# working.net
KiCad netlist of a schematic drawn in EAGLE
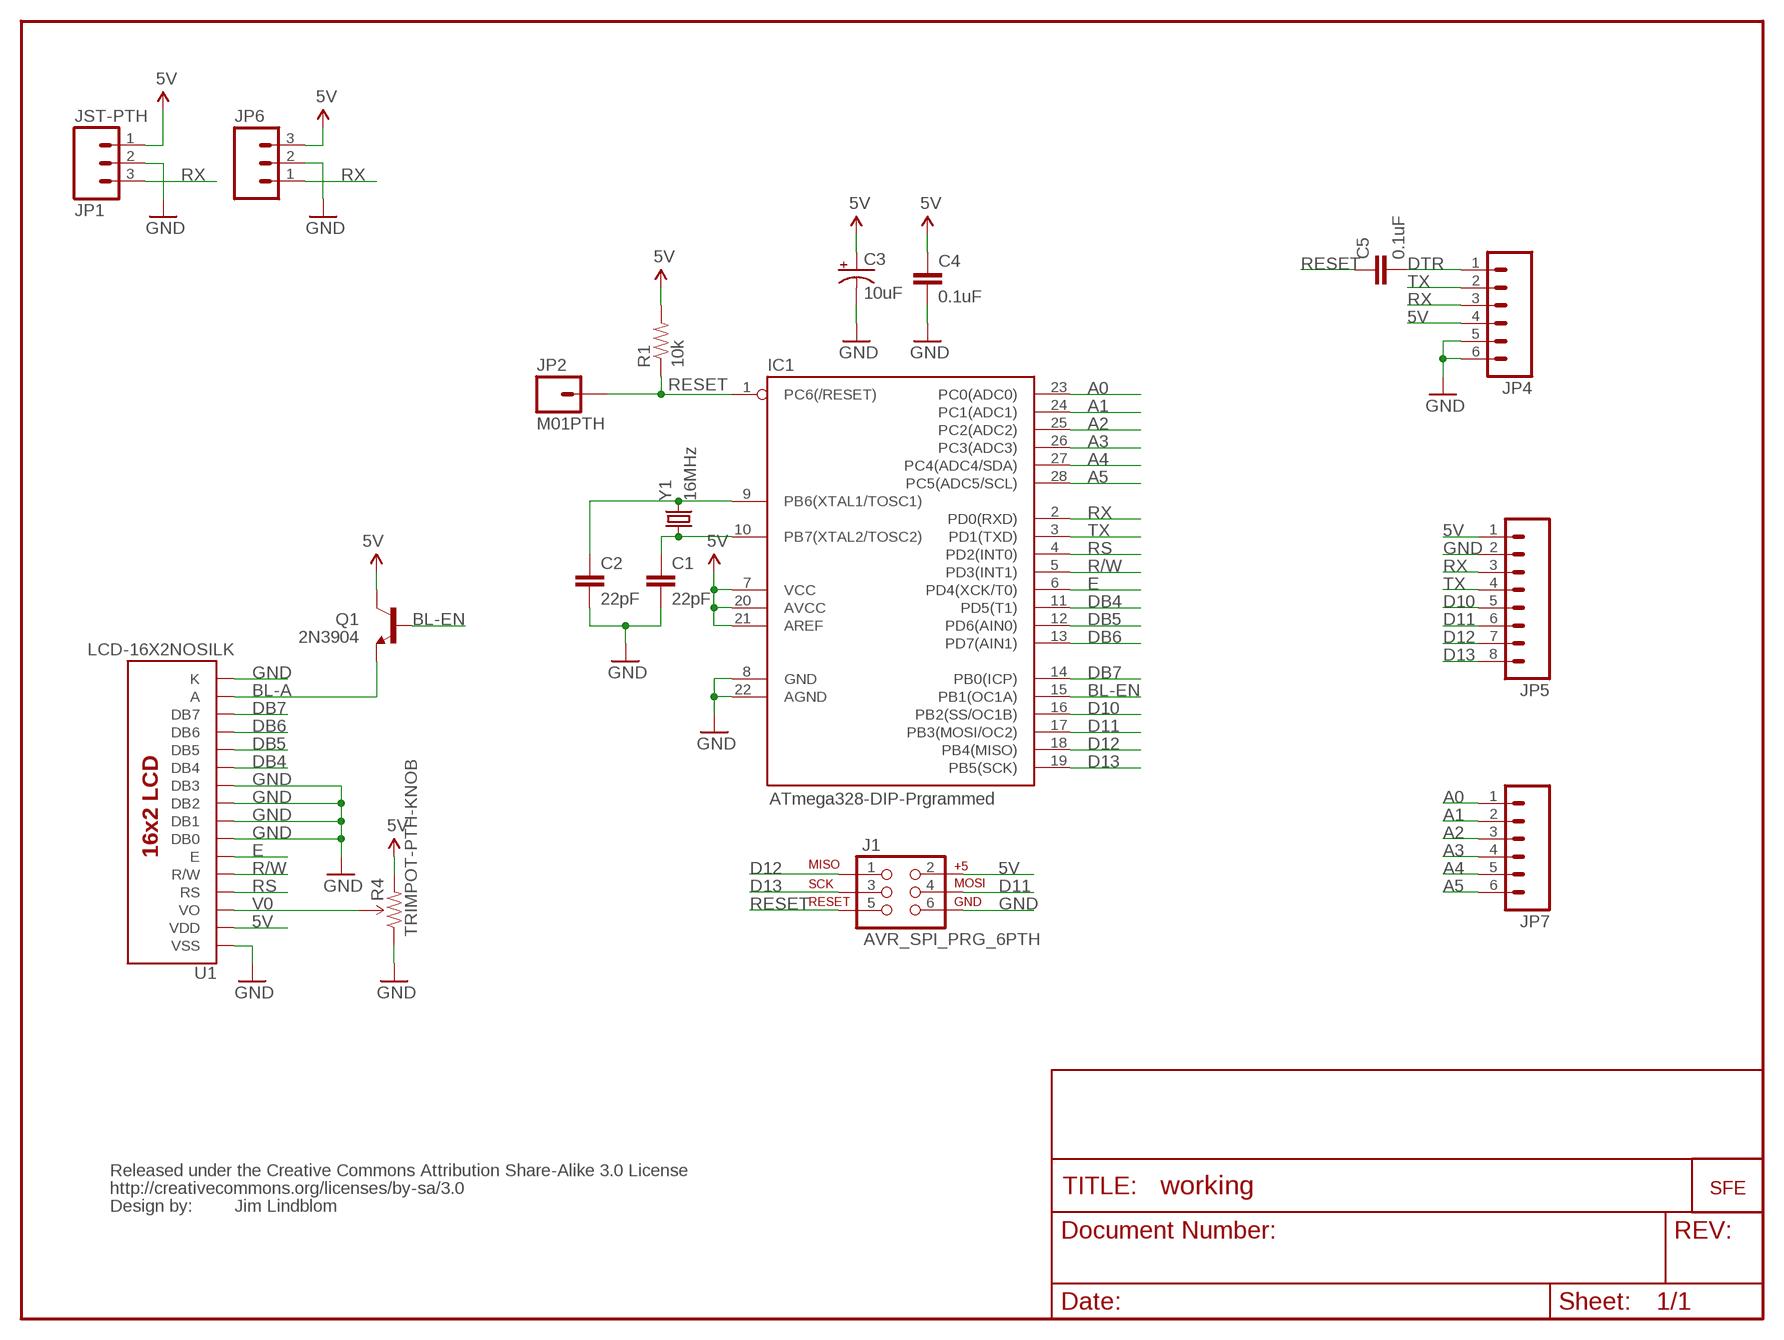
[diagram p0: schematic, sheet 1]

(export (version "E")
  (design (tool "Eeschema 10.0.6"))
  (components
    (comp (ref "C1")
      (value "22pF")
      (footprint "eagle-import:CAP-PTH-SMALL2")
      (libsource (lib "eagle-import") (part "CAPPTH2"))
    )
    (comp (ref "C2")
      (value "22pF")
      (footprint "eagle-import:CAP-PTH-SMALL2")
      (libsource (lib "eagle-import") (part "CAPPTH2"))
    )
    (comp (ref "C3")
      (value "10uF")
      (footprint "eagle-import:CPOL-RADIAL-10UF-25V")
      (libsource (lib "eagle-import") (part "CAP_POLPTH2"))
    )
    (comp (ref "C4")
      (value "0.1uF")
      (footprint "eagle-import:CAP-PTH-SMALL2")
      (libsource (lib "eagle-import") (part "CAPPTH2"))
    )
    (comp (ref "C5")
      (value "0.1uF")
      (footprint "eagle-import:CAP-PTH-SMALL2")
      (libsource (lib "eagle-import") (part "CAPPTH2"))
    )
    (comp (ref "IC1")
      (value "ATmega328-DIP-Prgrammed")
      (footprint "eagle-import:DIL28-3")
      (libsource (lib "eagle-import") (part "AVR-MEGA8-PPTH"))
    )
    (comp (ref "J1")
      (value "AVR_SPI_PRG_6PTH")
      (footprint "eagle-import:2X3")
      (libsource (lib "eagle-import") (part "AVR_SPI_PRG_6PTH"))
    )
    (comp (ref "JP1")
      (value "JST-PTH")
      (footprint "eagle-import:JST-3-PTH")
      (libsource (lib "eagle-import") (part "M03JST-PTH"))
    )
    (comp (ref "JP2")
      (value "M01PTH")
      (footprint "eagle-import:1X01")
      (libsource (lib "eagle-import") (part "M01PTH"))
    )
    (comp (ref "JP3")
      (value "LOGO-SFENEW")
      (footprint "eagle-import:SFE-NEW-WEBLOGO")
      (libsource (lib "eagle-import") (part "LOGO-SFENEW"))
    )
    (comp (ref "JP4")
      (value "M06SIP")
      (footprint "eagle-import:1X06")
      (libsource (lib "eagle-import") (part "M06SIP"))
    )
    (comp (ref "JP5")
      (value "M08")
      (footprint "eagle-import:1X08")
      (libsource (lib "eagle-import") (part "M08"))
    )
    (comp (ref "JP6")
      (value "M03PTH")
      (footprint "eagle-import:1X03")
      (libsource (lib "eagle-import") (part "M03PTH"))
    )
    (comp (ref "JP7")
      (value "M06SIP")
      (footprint "eagle-import:1X06")
      (libsource (lib "eagle-import") (part "M06SIP"))
    )
    (comp (ref "Q1")
      (value "2N3904")
      (footprint "eagle-import:TO-92")
      (libsource (lib "eagle-import") (part "TRANSISTOR_NPNTO92"))
    )
    (comp (ref "R1")
      (value "10k")
      (footprint "eagle-import:AXIAL-0.3")
      (libsource (lib "eagle-import") (part "RESISTORAXIAL-0.3"))
    )
    (comp (ref "R4")
      (value "TRIMPOT-PTH-KNOB")
      (footprint "eagle-import:3386U")
      (libsource (lib "eagle-import") (part "TRIMPOT-PTH-KNOB"))
    )
    (comp (ref "U$4")
      (value "CREATIVE_COMMONS")
      (footprint "eagle-import:CREATIVE_COMMONS")
      (libsource (lib "eagle-import") (part "CREATIVE_COMMONS"))
    )
    (comp (ref "U1")
      (value "LCD-16X2NOSILK")
      (footprint "eagle-import:LCD-16X2_NOSILK")
      (libsource (lib "eagle-import") (part "LCD-16X2NOSILK"))
    )
    (comp (ref "Y1")
      (value "16MHz")
      (footprint "eagle-import:HC49US")
      (libsource (lib "eagle-import") (part "CRYSTALHC49US"))
    )
  )
  (nets
    (net (code "1") (name "/A0") (class "Default")
      (node (ref "IC1") (pin "23") (pinfunction "PC0(ADC0)_23") (pintype "bidirectional"))
      (node (ref "JP7") (pin "1") (pinfunction "1_1") (pintype "passive"))
    )
    (net (code "2") (name "/A1") (class "Default")
      (node (ref "IC1") (pin "24") (pinfunction "PC1(ADC1)_24") (pintype "bidirectional"))
      (node (ref "JP7") (pin "2") (pinfunction "2_2") (pintype "passive"))
    )
    (net (code "3") (name "/A2") (class "Default")
      (node (ref "IC1") (pin "25") (pinfunction "PC2(ADC2)_25") (pintype "bidirectional"))
      (node (ref "JP7") (pin "3") (pinfunction "3_3") (pintype "passive"))
    )
    (net (code "4") (name "/A3") (class "Default")
      (node (ref "IC1") (pin "26") (pinfunction "PC3(ADC3)_26") (pintype "bidirectional"))
      (node (ref "JP7") (pin "4") (pinfunction "4_4") (pintype "passive"))
    )
    (net (code "5") (name "/A4") (class "Default")
      (node (ref "IC1") (pin "27") (pinfunction "PC4(ADC4/SDA)_27") (pintype "bidirectional"))
      (node (ref "JP7") (pin "5") (pinfunction "5_5") (pintype "passive"))
    )
    (net (code "6") (name "/A5") (class "Default")
      (node (ref "IC1") (pin "28") (pinfunction "PC5(ADC5/SCL)_28") (pintype "bidirectional"))
      (node (ref "JP7") (pin "6") (pinfunction "6_6") (pintype "passive"))
    )
    (net (code "7") (name "/BL-A") (class "Default")
      (node (ref "Q1") (pin "1") (pinfunction "E_1") (pintype "passive"))
      (node (ref "U1") (pin "15") (pinfunction "A_15") (pintype "power_in"))
    )
    (net (code "8") (name "/BL-EN") (class "Default")
      (node (ref "IC1") (pin "15") (pinfunction "PB1(OC1A)_15") (pintype "bidirectional"))
      (node (ref "Q1") (pin "2") (pinfunction "B_2") (pintype "passive"))
    )
    (net (code "9") (name "/D10") (class "Default")
      (node (ref "IC1") (pin "16") (pinfunction "PB2(SS/OC1B)_16") (pintype "bidirectional"))
      (node (ref "JP5") (pin "5") (pinfunction "5_5") (pintype "passive"))
    )
    (net (code "10") (name "/D11") (class "Default")
      (node (ref "IC1") (pin "17") (pinfunction "PB3(MOSI/OC2)_17") (pintype "bidirectional"))
      (node (ref "J1") (pin "4") (pinfunction "4_4") (pintype "passive"))
      (node (ref "JP5") (pin "6") (pinfunction "6_6") (pintype "passive"))
    )
    (net (code "11") (name "/D12") (class "Default")
      (node (ref "IC1") (pin "18") (pinfunction "PB4(MISO)_18") (pintype "bidirectional"))
      (node (ref "J1") (pin "1") (pinfunction "1_1") (pintype "passive"))
      (node (ref "JP5") (pin "7") (pinfunction "7_7") (pintype "passive"))
    )
    (net (code "12") (name "/D13") (class "Default")
      (node (ref "IC1") (pin "19") (pinfunction "PB5(SCK)_19") (pintype "bidirectional"))
      (node (ref "J1") (pin "3") (pinfunction "3_3") (pintype "passive"))
      (node (ref "JP5") (pin "8") (pinfunction "8_8") (pintype "passive"))
    )
    (net (code "13") (name "/DB4") (class "Default")
      (node (ref "IC1") (pin "11") (pinfunction "PD5(T1)_11") (pintype "bidirectional"))
      (node (ref "U1") (pin "11") (pinfunction "DB4_11") (pintype "bidirectional"))
    )
    (net (code "14") (name "/DB5") (class "Default")
      (node (ref "IC1") (pin "12") (pinfunction "PD6(AIN0)_12") (pintype "bidirectional"))
      (node (ref "U1") (pin "12") (pinfunction "DB5_12") (pintype "bidirectional"))
    )
    (net (code "15") (name "/DB6") (class "Default")
      (node (ref "IC1") (pin "13") (pinfunction "PD7(AIN1)_13") (pintype "bidirectional"))
      (node (ref "U1") (pin "13") (pinfunction "DB6_13") (pintype "bidirectional"))
    )
    (net (code "16") (name "/DB7") (class "Default")
      (node (ref "IC1") (pin "14") (pinfunction "PB0(ICP)_14") (pintype "bidirectional"))
      (node (ref "U1") (pin "14") (pinfunction "DB7_14") (pintype "bidirectional"))
    )
    (net (code "17") (name "/DTR") (class "Default")
      (node (ref "C5") (pin "2") (pinfunction "2_2") (pintype "passive"))
      (node (ref "JP4") (pin "1") (pinfunction "1_1") (pintype "passive"))
    )
    (net (code "18") (name "/E") (class "Default")
      (node (ref "IC1") (pin "6") (pinfunction "PD4(XCK/T0)_6") (pintype "bidirectional"))
      (node (ref "U1") (pin "6") (pinfunction "E_6") (pintype "input"))
    )
    (net (code "19") (name "/RESET") (class "Default")
      (node (ref "C5") (pin "1") (pinfunction "1_1") (pintype "passive"))
      (node (ref "IC1") (pin "1") (pinfunction "PC6(/RESET)_1") (pintype "bidirectional"))
      (node (ref "J1") (pin "5") (pinfunction "5_5") (pintype "passive"))
      (node (ref "JP2") (pin "1") (pinfunction "1_1") (pintype "passive"))
      (node (ref "R1") (pin "P$1") (pinfunction "1_P$1") (pintype "passive"))
    )
    (net (code "20") (name "/RS") (class "Default")
      (node (ref "IC1") (pin "4") (pinfunction "PD2(INT0)_4") (pintype "bidirectional"))
      (node (ref "U1") (pin "4") (pinfunction "RS_4") (pintype "input"))
    )
    (net (code "21") (name "/RX") (class "Default")
      (node (ref "IC1") (pin "2") (pinfunction "PD0(RXD)_2") (pintype "bidirectional"))
      (node (ref "JP1") (pin "3") (pinfunction "3_3") (pintype "passive"))
      (node (ref "JP4") (pin "3") (pinfunction "3_3") (pintype "passive"))
      (node (ref "JP5") (pin "3") (pinfunction "3_3") (pintype "passive"))
      (node (ref "JP6") (pin "1") (pinfunction "1_1") (pintype "passive"))
    )
    (net (code "22") (name "/R{slash}W") (class "Default")
      (node (ref "IC1") (pin "5") (pinfunction "PD3(INT1)_5") (pintype "bidirectional"))
      (node (ref "U1") (pin "5") (pinfunction "R/W_5") (pintype "input"))
    )
    (net (code "23") (name "/TX") (class "Default")
      (node (ref "IC1") (pin "3") (pinfunction "PD1(TXD)_3") (pintype "bidirectional"))
      (node (ref "JP4") (pin "2") (pinfunction "2_2") (pintype "passive"))
      (node (ref "JP5") (pin "4") (pinfunction "4_4") (pintype "passive"))
    )
    (net (code "24") (name "/V0") (class "Default")
      (node (ref "R4") (pin "2") (pinfunction "WIPER_2") (pintype "passive"))
      (node (ref "U1") (pin "3") (pinfunction "VO_3") (pintype "bidirectional"))
    )
    (net (code "25") (name "5V") (class "Default")
      (node (ref "C3") (pin "1") (pinfunction "+_1") (pintype "passive"))
      (node (ref "C4") (pin "1") (pinfunction "1_1") (pintype "passive"))
      (node (ref "IC1") (pin "20") (pinfunction "AVCC_20") (pintype "bidirectional"))
      (node (ref "IC1") (pin "21") (pinfunction "AREF_21") (pintype "bidirectional"))
      (node (ref "IC1") (pin "7") (pinfunction "VCC_7") (pintype "bidirectional"))
      (node (ref "J1") (pin "2") (pinfunction "2_2") (pintype "passive"))
      (node (ref "JP1") (pin "1") (pinfunction "1_1") (pintype "passive"))
      (node (ref "JP4") (pin "4") (pinfunction "4_4") (pintype "passive"))
      (node (ref "JP5") (pin "1") (pinfunction "1_1") (pintype "passive"))
      (node (ref "JP6") (pin "3") (pinfunction "3_3") (pintype "passive"))
      (node (ref "Q1") (pin "3") (pinfunction "C_3") (pintype "passive"))
      (node (ref "R1") (pin "P$2") (pinfunction "2_P$2") (pintype "passive"))
      (node (ref "R4") (pin "3") (pinfunction "CW_3") (pintype "passive"))
      (node (ref "U1") (pin "2") (pinfunction "VDD_2") (pintype "power_in"))
    )
    (net (code "26") (name "GND") (class "Default")
      (node (ref "C1") (pin "2") (pinfunction "2_2") (pintype "passive"))
      (node (ref "C2") (pin "2") (pinfunction "2_2") (pintype "passive"))
      (node (ref "C3") (pin "2") (pinfunction "-_2") (pintype "passive"))
      (node (ref "C4") (pin "2") (pinfunction "2_2") (pintype "passive"))
      (node (ref "IC1") (pin "22") (pinfunction "AGND_22") (pintype "bidirectional"))
      (node (ref "IC1") (pin "8") (pinfunction "GND_8") (pintype "bidirectional"))
      (node (ref "J1") (pin "6") (pinfunction "6_6") (pintype "passive"))
      (node (ref "JP1") (pin "2") (pinfunction "2_2") (pintype "passive"))
      (node (ref "JP4") (pin "5") (pinfunction "5_5") (pintype "passive"))
      (node (ref "JP4") (pin "6") (pinfunction "6_6") (pintype "passive"))
      (node (ref "JP5") (pin "2") (pinfunction "2_2") (pintype "passive"))
      (node (ref "JP6") (pin "2") (pinfunction "2_2") (pintype "passive"))
      (node (ref "R4") (pin "1") (pinfunction "CCW_1") (pintype "passive"))
      (node (ref "U1") (pin "1") (pinfunction "VSS_1") (pintype "power_in"))
      (node (ref "U1") (pin "10") (pinfunction "DB3_10") (pintype "bidirectional"))
      (node (ref "U1") (pin "16") (pinfunction "K_16") (pintype "power_in"))
      (node (ref "U1") (pin "7") (pinfunction "DB0_7") (pintype "bidirectional"))
      (node (ref "U1") (pin "8") (pinfunction "DB1_8") (pintype "bidirectional"))
      (node (ref "U1") (pin "9") (pinfunction "DB2_9") (pintype "bidirectional"))
    )
    (net (code "27") (name "Net-(IC1-PB6(XTAL1{slash}TOSC1))") (class "Default")
      (node (ref "C2") (pin "1") (pinfunction "1_1") (pintype "passive"))
      (node (ref "IC1") (pin "9") (pinfunction "PB6(XTAL1/TOSC1)_9") (pintype "bidirectional"))
      (node (ref "Y1") (pin "2") (pinfunction "2_2") (pintype "passive"))
    )
    (net (code "28") (name "Net-(IC1-PB7(XTAL2{slash}TOSC2))") (class "Default")
      (node (ref "C1") (pin "1") (pinfunction "1_1") (pintype "passive"))
      (node (ref "IC1") (pin "10") (pinfunction "PB7(XTAL2/TOSC2)_10") (pintype "bidirectional"))
      (node (ref "Y1") (pin "1") (pinfunction "1_1") (pintype "passive"))
    )
  )
)
